# Eingangsschaltung.net
KiCad netlist of a schematic drawn in EAGLE
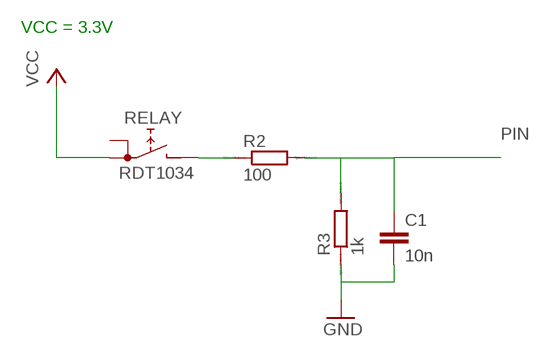
[diagram p0: schematic, sheet 1]

(export (version "E")
  (design (tool "Eeschema 10.0.6"))
  (components
    (comp (ref "C1")
      (value "10n")
      (footprint "eagle-import:C025-025X050")
      (libsource (lib "eagle-import") (part "C-EU025-025X050"))
    )
    (comp (ref "R2")
      (value "100")
      (footprint "eagle-import:0204_7")
      (libsource (lib "eagle-import") (part "R0204/7"))
    )
    (comp (ref "R3")
      (value "1k")
      (footprint "eagle-import:0204_7")
      (libsource (lib "eagle-import") (part "R0204/7"))
    )
    (comp (ref "RELAY")
      (value "RDT1034")
      (footprint "eagle-import:RDT1034")
      (libsource (lib "eagle-import") (part "RDT1034"))
    )
  )
  (nets
    (net (code "1") (name "/PIN") (class "Default")
      (node (ref "C1") (pin "1") (pinfunction "1_1") (pintype "passive"))
      (node (ref "R2") (pin "2") (pinfunction "2_2") (pintype "passive"))
      (node (ref "R3") (pin "2") (pinfunction "2_2") (pintype "passive"))
    )
    (net (code "2") (name "GND") (class "Default")
      (node (ref "C1") (pin "2") (pinfunction "2_2") (pintype "passive"))
      (node (ref "R3") (pin "1") (pinfunction "1_1") (pintype "passive"))
    )
    (net (code "3") (name "Net-(R2-Pad1)") (class "Default")
      (node (ref "R2") (pin "1") (pinfunction "1_1") (pintype "passive"))
      (node (ref "RELAY") (pin "B") (pinfunction "B_B") (pintype "passive"))
    )
    (net (code "4") (name "VCC") (class "Default")
      (node (ref "RELAY") (pin "A1") (pinfunction "A1_A1") (pintype "passive"))
    )
    (net (code "5") (name "unconnected-(RELAY-PadA)") (class "Default")
      (node (ref "RELAY") (pin "A") (pinfunction "A_A") (pintype "passive"))
    )
  )
)
